# mini_optron.net
KiCad netlist of a schematic drawn in EAGLE
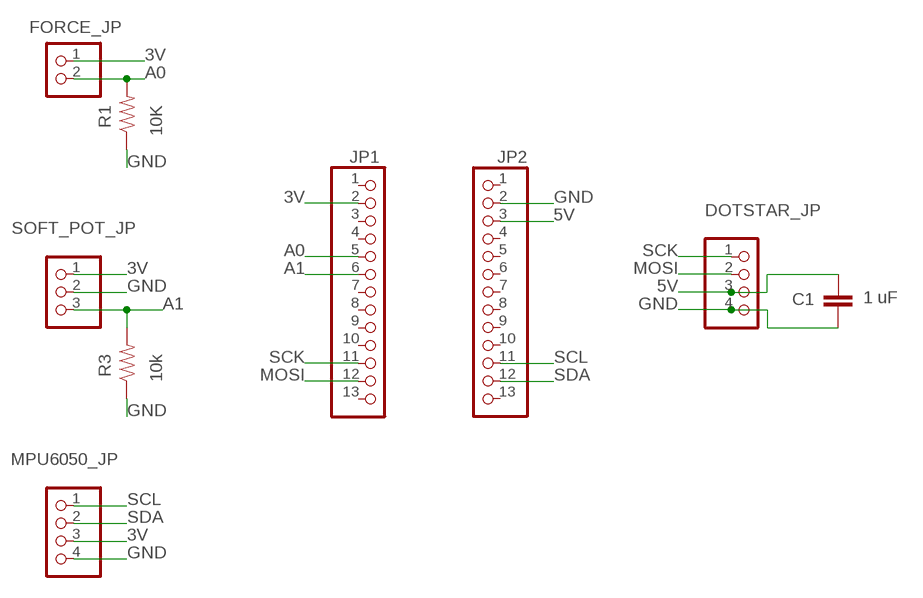
[diagram p0: schematic, sheet 1]

(export (version "E")
  (design (tool "Eeschema 10.0.6"))
  (components
    (comp (ref "C1")
      (value "1 uF")
      (footprint "eagle-import:C5B7.2")
      (fields (field (name "MF") "AVX") (field (name "MPN") "0805YD105KAT2A"))
      (libsource (lib "eagle-import") (part "C5/7.2"))
    )
    (comp (ref "DOTSTAR_JP")
      (value "PINHD-1X4")
      (footprint "eagle-import:1X04")
      (libsource (lib "eagle-import") (part "PINHD-1X4"))
    )
    (comp (ref "FORCE_JP")
      (value "PINHD-1X2")
      (footprint "eagle-import:1X02")
      (libsource (lib "eagle-import") (part "PINHD-1X2"))
    )
    (comp (ref "JP1")
      (value "PINHD-1X13_BIG")
      (footprint "eagle-import:1X13-BIG")
      (libsource (lib "eagle-import") (part "PINHD-1X13_BIG"))
    )
    (comp (ref "JP2")
      (value "PINHD-1X13_BIG")
      (footprint "eagle-import:1X13-BIG")
      (libsource (lib "eagle-import") (part "PINHD-1X13_BIG"))
    )
    (comp (ref "MPU6050_JP")
      (value "PINHD-1X4")
      (footprint "eagle-import:1X04")
      (libsource (lib "eagle-import") (part "PINHD-1X4"))
    )
    (comp (ref "R1")
      (value "10K")
      (footprint "eagle-import:AXIAL-0.3")
      (fields (field (name "MF") "VISHAY") (field (name "MPN") "CRCW060310K0FKEA"))
      (libsource (lib "eagle-import") (part "RESISTORAXIAL-0.3"))
    )
    (comp (ref "R3")
      (value "10k")
      (footprint "eagle-import:AXIAL-0.3")
      (fields (field (name "MF") "VISHAY") (field (name "MPN") "CRCW060310K0FKEA"))
      (libsource (lib "eagle-import") (part "RESISTORAXIAL-0.3"))
    )
    (comp (ref "SOFT_POT_JP")
      (value "PINHD-1X3")
      (footprint "eagle-import:1X03")
      (libsource (lib "eagle-import") (part "PINHD-1X3"))
    )
  )
  (nets
    (net (code "1") (name "/3V") (class "Default")
      (node (ref "FORCE_JP") (pin "1") (pinfunction "1_1") (pintype "passive"))
      (node (ref "JP1") (pin "2") (pinfunction "2_2") (pintype "passive"))
      (node (ref "MPU6050_JP") (pin "3") (pinfunction "3_3") (pintype "passive"))
      (node (ref "SOFT_POT_JP") (pin "1") (pinfunction "1_1") (pintype "passive"))
    )
    (net (code "2") (name "/5V") (class "Default")
      (node (ref "C1") (pin "1") (pinfunction "1_1") (pintype "passive"))
      (node (ref "DOTSTAR_JP") (pin "3") (pinfunction "3_3") (pintype "passive"))
      (node (ref "JP2") (pin "3") (pinfunction "3_3") (pintype "passive"))
    )
    (net (code "3") (name "/A0") (class "Default")
      (node (ref "FORCE_JP") (pin "2") (pinfunction "2_2") (pintype "passive"))
      (node (ref "JP1") (pin "5") (pinfunction "5_5") (pintype "passive"))
      (node (ref "R1") (pin "P$2") (pinfunction "2_P$2") (pintype "passive"))
    )
    (net (code "4") (name "/A1") (class "Default")
      (node (ref "JP1") (pin "6") (pinfunction "6_6") (pintype "passive"))
      (node (ref "R3") (pin "P$2") (pinfunction "2_P$2") (pintype "passive"))
      (node (ref "SOFT_POT_JP") (pin "3") (pinfunction "3_3") (pintype "passive"))
    )
    (net (code "5") (name "/GND") (class "Default")
      (node (ref "C1") (pin "2") (pinfunction "2_2") (pintype "passive"))
      (node (ref "DOTSTAR_JP") (pin "4") (pinfunction "4_4") (pintype "passive"))
      (node (ref "JP2") (pin "2") (pinfunction "2_2") (pintype "passive"))
      (node (ref "MPU6050_JP") (pin "4") (pinfunction "4_4") (pintype "passive"))
      (node (ref "R1") (pin "P$1") (pinfunction "1_P$1") (pintype "passive"))
      (node (ref "R3") (pin "P$1") (pinfunction "1_P$1") (pintype "passive"))
      (node (ref "SOFT_POT_JP") (pin "2") (pinfunction "2_2") (pintype "passive"))
    )
    (net (code "6") (name "/MOSI") (class "Default")
      (node (ref "DOTSTAR_JP") (pin "2") (pinfunction "2_2") (pintype "passive"))
      (node (ref "JP1") (pin "12") (pinfunction "12_12") (pintype "passive"))
    )
    (net (code "7") (name "/SCK") (class "Default")
      (node (ref "DOTSTAR_JP") (pin "1") (pinfunction "1_1") (pintype "passive"))
      (node (ref "JP1") (pin "11") (pinfunction "11_11") (pintype "passive"))
    )
    (net (code "8") (name "/SCL") (class "Default")
      (node (ref "JP2") (pin "11") (pinfunction "11_11") (pintype "passive"))
      (node (ref "MPU6050_JP") (pin "1") (pinfunction "1_1") (pintype "passive"))
    )
    (net (code "9") (name "/SDA") (class "Default")
      (node (ref "JP2") (pin "12") (pinfunction "12_12") (pintype "passive"))
      (node (ref "MPU6050_JP") (pin "2") (pinfunction "2_2") (pintype "passive"))
    )
    (net (code "10") (name "unconnected-(JP1-Pad1)") (class "Default")
      (node (ref "JP1") (pin "1") (pinfunction "1_1") (pintype "passive"))
    )
    (net (code "11") (name "unconnected-(JP1-Pad3)") (class "Default")
      (node (ref "JP1") (pin "3") (pinfunction "3_3") (pintype "passive"))
    )
    (net (code "12") (name "unconnected-(JP1-Pad4)") (class "Default")
      (node (ref "JP1") (pin "4") (pinfunction "4_4") (pintype "passive"))
    )
    (net (code "13") (name "unconnected-(JP1-Pad7)") (class "Default")
      (node (ref "JP1") (pin "7") (pinfunction "7_7") (pintype "passive"))
    )
    (net (code "14") (name "unconnected-(JP1-Pad8)") (class "Default")
      (node (ref "JP1") (pin "8") (pinfunction "8_8") (pintype "passive"))
    )
    (net (code "15") (name "unconnected-(JP1-Pad9)") (class "Default")
      (node (ref "JP1") (pin "9") (pinfunction "9_9") (pintype "passive"))
    )
    (net (code "16") (name "unconnected-(JP1-Pad10)") (class "Default")
      (node (ref "JP1") (pin "10") (pinfunction "10_10") (pintype "passive"))
    )
    (net (code "17") (name "unconnected-(JP1-Pad13)") (class "Default")
      (node (ref "JP1") (pin "13") (pinfunction "13_13") (pintype "passive"))
    )
    (net (code "18") (name "unconnected-(JP2-Pad1)") (class "Default")
      (node (ref "JP2") (pin "1") (pinfunction "1_1") (pintype "passive"))
    )
    (net (code "19") (name "unconnected-(JP2-Pad4)") (class "Default")
      (node (ref "JP2") (pin "4") (pinfunction "4_4") (pintype "passive"))
    )
    (net (code "20") (name "unconnected-(JP2-Pad5)") (class "Default")
      (node (ref "JP2") (pin "5") (pinfunction "5_5") (pintype "passive"))
    )
    (net (code "21") (name "unconnected-(JP2-Pad6)") (class "Default")
      (node (ref "JP2") (pin "6") (pinfunction "6_6") (pintype "passive"))
    )
    (net (code "22") (name "unconnected-(JP2-Pad7)") (class "Default")
      (node (ref "JP2") (pin "7") (pinfunction "7_7") (pintype "passive"))
    )
    (net (code "23") (name "unconnected-(JP2-Pad8)") (class "Default")
      (node (ref "JP2") (pin "8") (pinfunction "8_8") (pintype "passive"))
    )
    (net (code "24") (name "unconnected-(JP2-Pad9)") (class "Default")
      (node (ref "JP2") (pin "9") (pinfunction "9_9") (pintype "passive"))
    )
    (net (code "25") (name "unconnected-(JP2-Pad10)") (class "Default")
      (node (ref "JP2") (pin "10") (pinfunction "10_10") (pintype "passive"))
    )
    (net (code "26") (name "unconnected-(JP2-Pad13)") (class "Default")
      (node (ref "JP2") (pin "13") (pinfunction "13_13") (pintype "passive"))
    )
  )
)
